# oled_control.net
KiCad netlist of a schematic drawn in Altium Designer
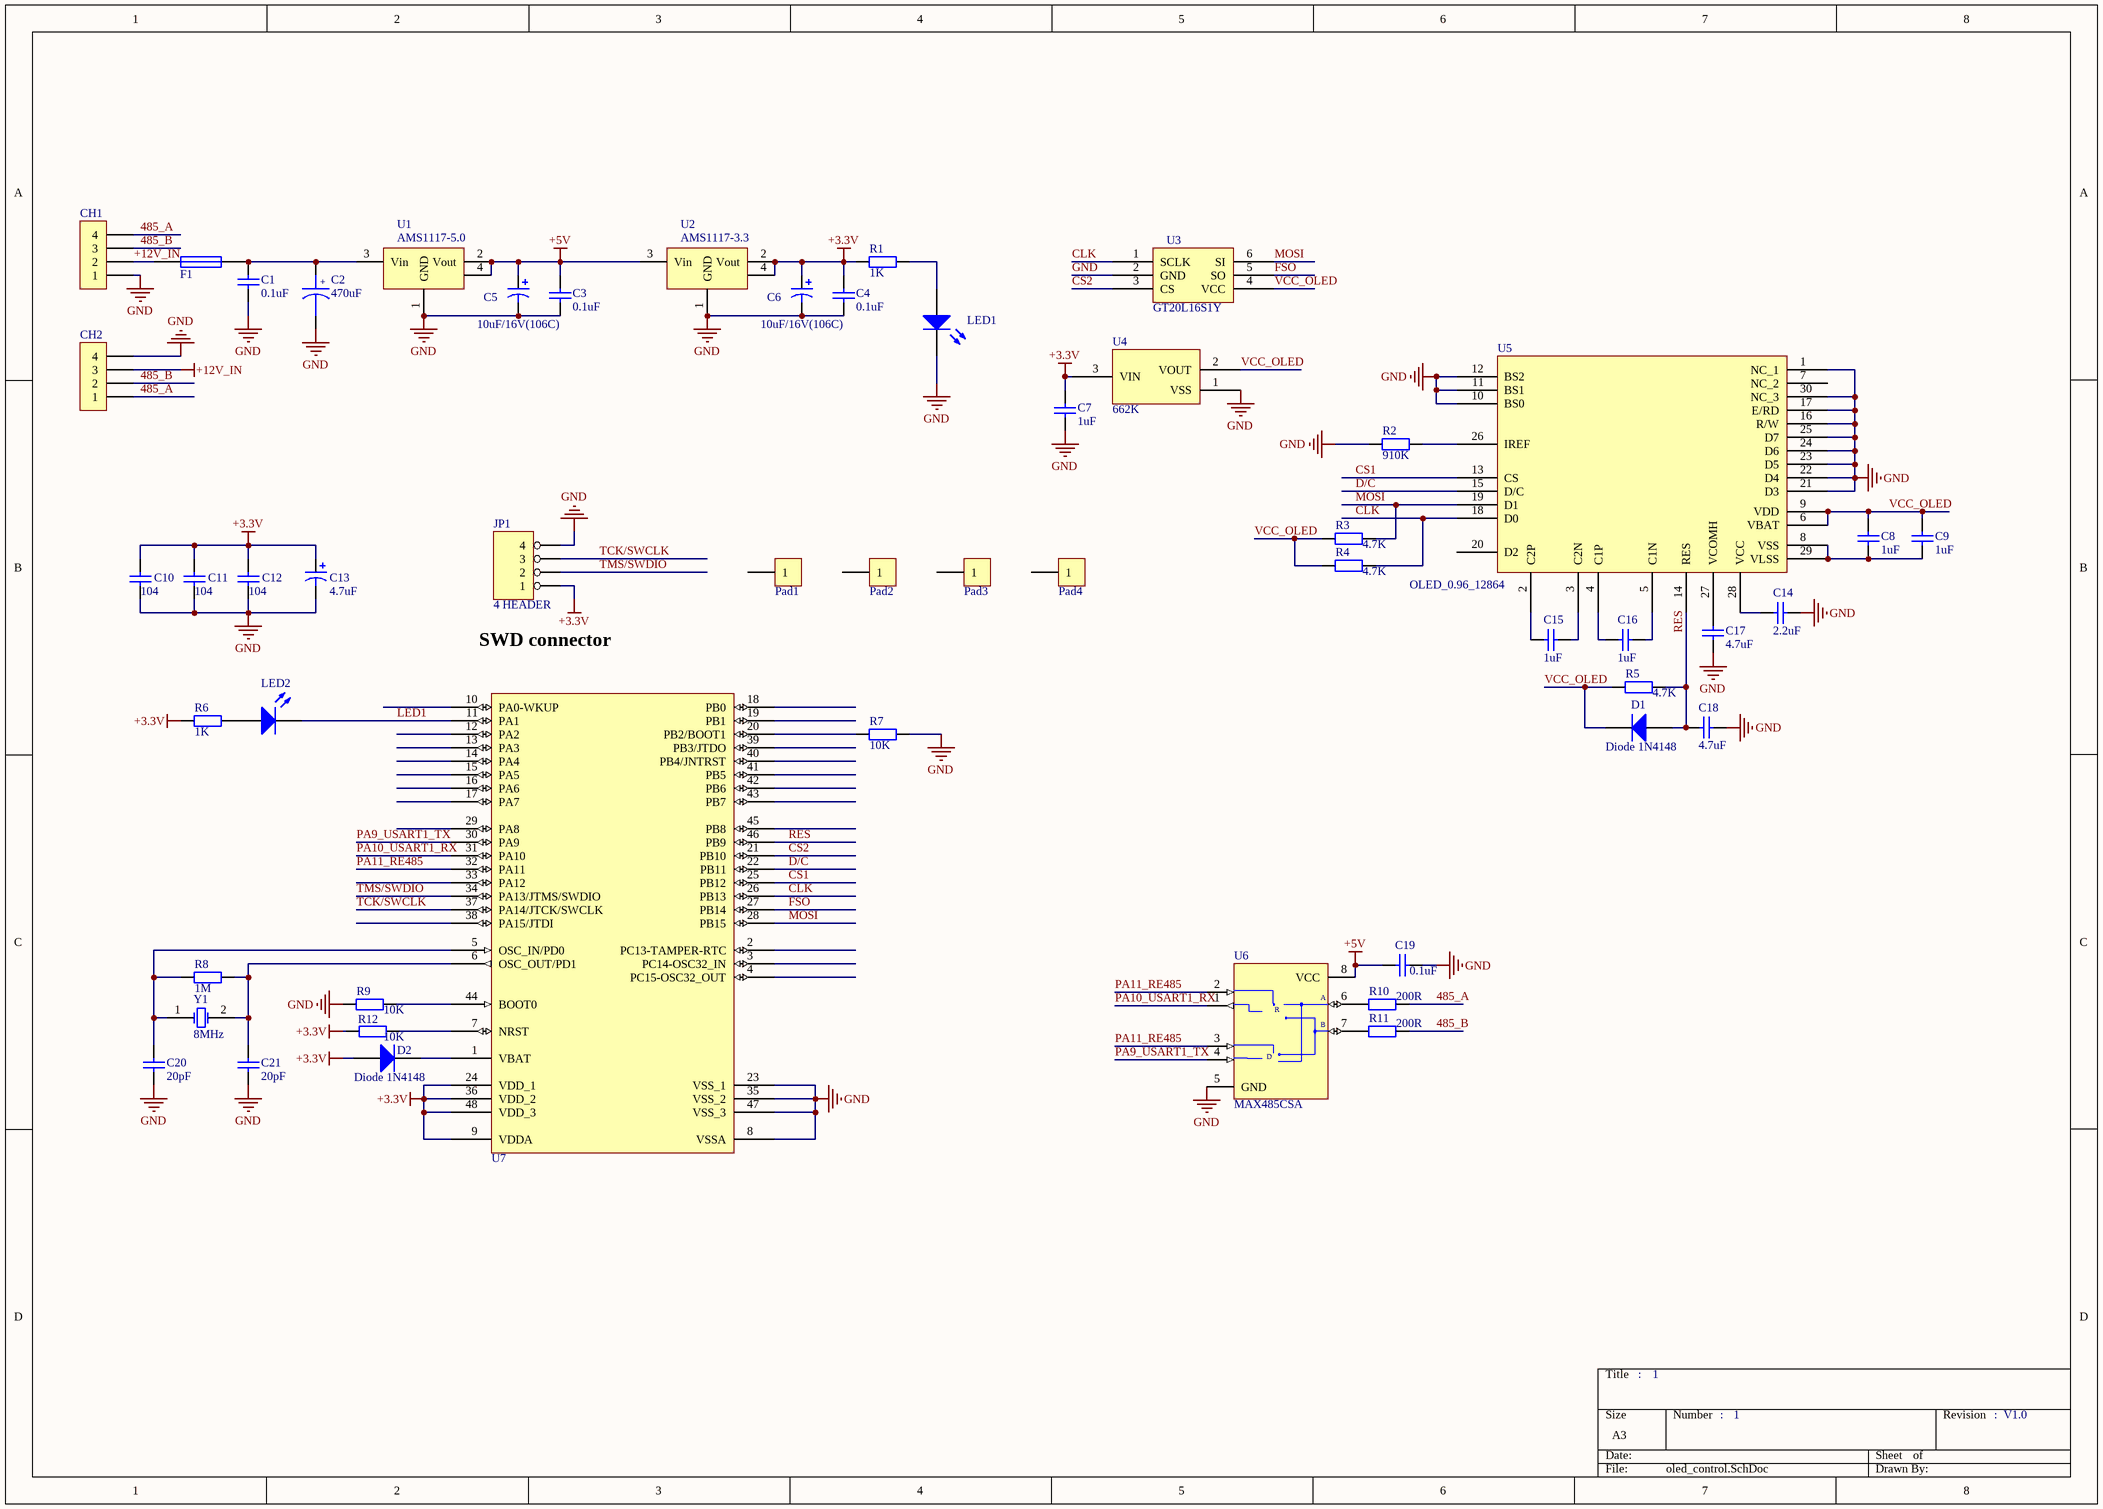
[diagram p0: oled_control.SchDoc]

(export (version "E")
  (design (tool "Eeschema 10.0.6"))
  (components
    (comp (ref "C1")
      (value "0.1uF")
      (footprint "0805")
      (description "Capacitor")
      (fields (field (name "Comment") "Cap") (field (name "PUBLISHER") "Altium Limited"))
      (libsource (lib "Miscellaneous Devices") (part "Cap"))
    )
    (comp (ref "C2")
      (value "C_2200uF")
      (footprint "C5*10")
      (fields (field (name "ALTIUM_UNNAMED_1") "470uF"))
      (libsource (lib "myIntegrated_Library1") (part "C_2200uF"))
    )
    (comp (ref "C3")
      (value "0.1uF")
      (footprint "0805")
      (description "Capacitor")
      (fields (field (name "Comment") "Cap") (field (name "PUBLISHER") "Altium Limited"))
      (libsource (lib "Miscellaneous Devices") (part "Cap"))
    )
    (comp (ref "C4")
      (value "0.1uF")
      (footprint "0805")
      (description "Capacitor")
      (fields (field (name "Comment") "Cap") (field (name "PUBLISHER") "Altium Limited"))
      (libsource (lib "Miscellaneous Devices") (part "Cap"))
    )
    (comp (ref "C5")
      (value "10uF/16V(106C)")
      (footprint "CAP A-3216")
      (description "Polarized Capacitor (Surface Mount)")
      (fields (field (name "Comment") "Cap Pol3") (field (name "PUBLISHER") "Altium Limited"))
      (libsource (lib "Miscellaneous Devices") (part "Cap Pol3"))
    )
    (comp (ref "C6")
      (value "10uF/16V(106C)")
      (footprint "CAP A-3216")
      (description "Polarized Capacitor (Surface Mount)")
      (fields (field (name "Comment") "Cap Pol3") (field (name "PUBLISHER") "Altium Limited"))
      (libsource (lib "Miscellaneous Devices") (part "Cap Pol3"))
    )
    (comp (ref "C7")
      (value "1uF")
      (footprint "0805")
      (description "Capacitor")
      (fields (field (name "Comment") "Cap") (field (name "PUBLISHER") "Altium Limited"))
      (libsource (lib "Miscellaneous Devices") (part "Cap"))
    )
    (comp (ref "C8")
      (value "1uF")
      (footprint "0805")
      (description "Capacitor")
      (fields (field (name "Comment") "Cap") (field (name "PUBLISHER") "Altium Limited"))
      (libsource (lib "Miscellaneous Devices") (part "Cap"))
    )
    (comp (ref "C9")
      (value "1uF")
      (footprint "0805")
      (description "Capacitor")
      (fields (field (name "Comment") "Cap") (field (name "PUBLISHER") "Altium Limited"))
      (libsource (lib "Miscellaneous Devices") (part "Cap"))
    )
    (comp (ref "C10")
      (value "104")
      (footprint "0805")
      (description "Capacitor")
      (fields (field (name "Comment") "Cap") (field (name "PUBLISHER") "Altium Limited"))
      (libsource (lib "Miscellaneous Devices") (part "Cap"))
    )
    (comp (ref "C11")
      (value "104")
      (footprint "0805")
      (description "Capacitor")
      (fields (field (name "Comment") "Cap") (field (name "PUBLISHER") "Altium Limited"))
      (libsource (lib "Miscellaneous Devices") (part "Cap"))
    )
    (comp (ref "C12")
      (value "104")
      (footprint "0805")
      (description "Capacitor")
      (fields (field (name "Comment") "Cap") (field (name "PUBLISHER") "Altium Limited"))
      (libsource (lib "Miscellaneous Devices") (part "Cap"))
    )
    (comp (ref "C13")
      (value "4.7uF")
      (footprint "3225[1210]")
      (description "Polarized Capacitor (Radial)")
      (fields (field (name "Comment") "Cap Pol1") (field (name "PUBLISHER") "Altium Limited"))
      (libsource (lib "Miscellaneous Devices") (part "Cap Pol1"))
    )
    (comp (ref "C14")
      (value "2.2uF")
      (footprint "0805")
      (description "Capacitor")
      (fields (field (name "Comment") "Cap") (field (name "PUBLISHER") "Altium Limited"))
      (libsource (lib "Miscellaneous Devices") (part "Cap"))
    )
    (comp (ref "C15")
      (value "1uF")
      (footprint "0805")
      (description "Capacitor")
      (fields (field (name "Comment") "Cap") (field (name "PUBLISHER") "Altium Limited"))
      (libsource (lib "Miscellaneous Devices") (part "Cap"))
    )
    (comp (ref "C16")
      (value "1uF")
      (footprint "0805")
      (description "Capacitor")
      (fields (field (name "Comment") "Cap") (field (name "PUBLISHER") "Altium Limited"))
      (libsource (lib "Miscellaneous Devices") (part "Cap"))
    )
    (comp (ref "C17")
      (value "4.7uF")
      (footprint "0805")
      (description "Capacitor")
      (fields (field (name "Comment") "Cap") (field (name "PUBLISHER") "Altium Limited"))
      (libsource (lib "Miscellaneous Devices") (part "Cap"))
    )
    (comp (ref "C18")
      (value "4.7uF")
      (footprint "0805")
      (description "Capacitor")
      (fields (field (name "Comment") "Cap") (field (name "PUBLISHER") "Altium Limited"))
      (libsource (lib "Miscellaneous Devices") (part "Cap"))
    )
    (comp (ref "C19")
      (value "0.1uF")
      (footprint "C0805tan")
      (description "Capacitor")
      (fields (field (name "Comment") "Cap") (field (name "PUBLISHER") "Altium Limited"))
      (libsource (lib "Miscellaneous Devices") (part "Cap"))
    )
    (comp (ref "C20")
      (value "20pF")
      (footprint "0805")
      (description "Capacitor")
      (fields (field (name "Comment") "Cap") (field (name "PUBLISHER") "Altium Limited"))
      (libsource (lib "开发板元件库") (part "Cap"))
    )
    (comp (ref "C21")
      (value "20pF")
      (footprint "0805")
      (description "Capacitor")
      (fields (field (name "Comment") "Cap") (field (name "PUBLISHER") "Altium Limited"))
      (libsource (lib "开发板元件库") (part "Cap"))
    )
    (comp (ref "CH1")
      (value "HEADER1X4")
      (footprint "CON4_1.5")
      (libsource (lib "myIntegrated_Library1") (part "HEADER1X4"))
    )
    (comp (ref "CH2")
      (value "HEADER1X4")
      (footprint "CON4_1.5")
      (libsource (lib "myIntegrated_Library1") (part "HEADER1X4"))
    )
    (comp (ref "D1")
      (value "Diode 1N4148")
      (footprint "LL34")
      (description "High Conductance Fast Diode")
      (fields (field (name "PUBLISHER") "Altium Limited"))
      (libsource (lib "Miscellaneous Devices") (part "Diode 1N4148"))
    )
    (comp (ref "D2")
      (value "Diode 1N4148")
      (footprint "LL34")
      (description "High Conductance Fast Diode")
      (fields (field (name "PUBLISHER") "Altium Limited"))
      (libsource (lib "Miscellaneous Devices") (part "Diode 1N4148"))
    )
    (comp (ref "F1")
      (value "FUSE")
      (footprint "3225[1210]")
      (libsource (lib "myIntegrated_Library1") (part "FUSE"))
    )
    (comp (ref "JP1")
      (value "4 HEADER")
      (footprint "CON4_1.5")
      (description "4 Pin Header")
      (libsource (lib "Miscellaneous Devices") (part "4 HEADER"))
    )
    (comp (ref "LED1")
      (value "~")
      (footprint "LED-0805")
      (description "Typical RED, GREEN, YELLOW, AMBER GaAs LED")
      (fields (field (name "PUBLISHER") "Altium Limited"))
      (libsource (lib "Miscellaneous Devices") (part "LED2"))
    )
    (comp (ref "LED2")
      (value "~")
      (footprint "LED-0805")
      (description "Typical RED, GREEN, YELLOW, AMBER GaAs LED")
      (fields (field (name "PUBLISHER") "Altium Limited"))
      (libsource (lib "Miscellaneous Devices") (part "LED2"))
    )
    (comp (ref "Pad1")
      (value "Pad")
      (footprint "pad35")
      (libsource (lib "myIntegrated_Library1") (part "Pad"))
    )
    (comp (ref "Pad2")
      (value "Pad")
      (footprint "pad35")
      (libsource (lib "myIntegrated_Library1") (part "Pad"))
    )
    (comp (ref "Pad3")
      (value "Pad")
      (footprint "pad35")
      (libsource (lib "myIntegrated_Library1") (part "Pad"))
    )
    (comp (ref "Pad4")
      (value "Pad")
      (footprint "pad35")
      (libsource (lib "myIntegrated_Library1") (part "Pad"))
    )
    (comp (ref "R1")
      (value "1K")
      (footprint "0805")
      (description "Resistor")
      (fields (field (name "Comment") "Res2") (field (name "PUBLISHER") "Altium Limited"))
      (libsource (lib "Miscellaneous Devices") (part "Res2"))
    )
    (comp (ref "R2")
      (value "910K")
      (footprint "0805")
      (description "Resistor")
      (fields (field (name "Comment") "Res2") (field (name "PUBLISHER") "Altium Limited"))
      (libsource (lib "Miscellaneous Devices") (part "Res2"))
    )
    (comp (ref "R3")
      (value "4.7K")
      (footprint "0805")
      (description "Resistor")
      (fields (field (name "Comment") "Res2") (field (name "PUBLISHER") "Altium Limited"))
      (libsource (lib "Miscellaneous Devices") (part "Res2"))
    )
    (comp (ref "R4")
      (value "4.7K")
      (footprint "0805")
      (description "Resistor")
      (fields (field (name "Comment") "Res2") (field (name "PUBLISHER") "Altium Limited"))
      (libsource (lib "Miscellaneous Devices") (part "Res2"))
    )
    (comp (ref "R5")
      (value "4.7K")
      (footprint "0805")
      (description "Resistor")
      (fields (field (name "Comment") "Res2") (field (name "PUBLISHER") "Altium Limited"))
      (libsource (lib "Miscellaneous Devices") (part "Res2"))
    )
    (comp (ref "R6")
      (value "1K")
      (footprint "0805")
      (description "Resistor")
      (fields (field (name "Comment") "Res2") (field (name "PUBLISHER") "Altium Limited"))
      (libsource (lib "Miscellaneous Devices") (part "Res2"))
    )
    (comp (ref "R7")
      (value "10K")
      (footprint "0805")
      (description "Resistor")
      (fields (field (name "Comment") "Res2") (field (name "PUBLISHER") "Altium Limited"))
      (libsource (lib "开发板元件库") (part "Res2"))
    )
    (comp (ref "R8")
      (value "1M")
      (footprint "0805")
      (description "Resistor")
      (fields (field (name "Comment") "Res2") (field (name "PUBLISHER") "Altium Limited"))
      (libsource (lib "开发板元件库") (part "Res2"))
    )
    (comp (ref "R9")
      (value "10K")
      (footprint "0805")
      (description "Resistor")
      (fields (field (name "Comment") "Res2") (field (name "PUBLISHER") "Altium Limited"))
      (libsource (lib "开发板元件库") (part "Res2"))
    )
    (comp (ref "R10")
      (value "200R")
      (footprint "C0805tan")
      (description "Resistor")
      (fields (field (name "Comment") "Res2") (field (name "PUBLISHER") "Altium Limited"))
      (libsource (lib "") (part "Res2_1"))
    )
    (comp (ref "R11")
      (value "200R")
      (footprint "C0805tan")
      (description "Resistor")
      (fields (field (name "Comment") "Res2") (field (name "PUBLISHER") "Altium Limited"))
      (libsource (lib "") (part "Res2_1"))
    )
    (comp (ref "R12")
      (value "10K")
      (footprint "0805")
      (description "Resistor")
      (fields (field (name "Comment") "Res2") (field (name "PUBLISHER") "Altium Limited"))
      (libsource (lib "开发板元件库") (part "Res2"))
    )
    (comp (ref "U1")
      (value "AMS1117-5.0")
      (footprint "SOT223")
      (libsource (lib "货架电子标签元件库") (part "AMS1117-5"))
    )
    (comp (ref "U2")
      (value "AMS1117-3.3")
      (footprint "SOT223")
      (libsource (lib "货架电子标签元件库") (part "AMS1117-5"))
    )
    (comp (ref "U3")
      (value "GT20L16S1Y")
      (footprint "SOT23-6")
      (libsource (lib "myIntegrated_Library1") (part "GT20L16S1Y"))
    )
    (comp (ref "U4")
      (value "662K")
      (footprint "SOT-23")
      (libsource (lib "myIntegrated_Library1") (part "662K"))
    )
    (comp (ref "U5")
      (value "OLED_0.96_12864")
      (footprint "OLED_0.96_12864")
      (libsource (lib "myIntegrated_Library1") (part "OLED_0.96_12864"))
    )
    (comp (ref "U6")
      (value "MAX485CSA")
      (footprint "NS08-L")
      (libsource (lib "myIntegrated_Library1") (part "MAX485CSA"))
    )
    (comp (ref "U7")
      (value "STM32F103C8T6")
      (footprint "LQFP48")
      (libsource (lib "myIntegrated_Library1") (part "STM32F103C8T6"))
    )
    (comp (ref "Y1")
      (value "8MHz")
      (footprint "XTAL_US")
      (description "Crystal Oscillator")
      (fields (field (name "PUBLISHER") "Altium Limited"))
      (libsource (lib "战舰STM32开发板底板封装库") (part "XTAL"))
    )
  )
  (nets
    (net (code "1") (name "+3.3V") (class "Default")
      (node (ref "C10") (pin "2") (pinfunction "2_2") (pintype "passive"))
      (node (ref "C11") (pin "2") (pinfunction "2_2") (pintype "passive"))
      (node (ref "C12") (pin "2") (pinfunction "2_2") (pintype "passive"))
      (node (ref "C13") (pin "1") (pinfunction "1_1") (pintype "passive"))
      (node (ref "C4") (pin "2") (pinfunction "2_2") (pintype "passive"))
      (node (ref "C6") (pin "1") (pinfunction "1_1") (pintype "passive"))
      (node (ref "C7") (pin "1") (pinfunction "1_1") (pintype "passive"))
      (node (ref "D2") (pin "1") (pinfunction "A_1") (pintype "passive"))
      (node (ref "JP1") (pin "1") (pinfunction "1_1") (pintype "passive"))
      (node (ref "R1") (pin "2") (pinfunction "2_2") (pintype "passive"))
      (node (ref "R12") (pin "1") (pinfunction "1_1") (pintype "passive"))
      (node (ref "R6") (pin "2") (pinfunction "2_2") (pintype "passive"))
      (node (ref "U2") (pin "2") (pinfunction "Vout_2") (pintype "passive"))
      (node (ref "U2") (pin "4") (pintype "passive"))
      (node (ref "U4") (pin "3") (pinfunction "VIN_3") (pintype "passive"))
      (node (ref "U7") (pin "24") (pinfunction "VDD_1_24") (pintype "power_in"))
      (node (ref "U7") (pin "36") (pinfunction "VDD_2_36") (pintype "power_in"))
      (node (ref "U7") (pin "48") (pinfunction "VDD_3_48") (pintype "power_in"))
      (node (ref "U7") (pin "9") (pinfunction "VDDA_9") (pintype "power_in"))
    )
    (net (code "2") (name "+5V") (class "Default")
      (node (ref "C19") (pin "1") (pinfunction "1_1") (pintype "passive"))
      (node (ref "C3") (pin "2") (pinfunction "2_2") (pintype "passive"))
      (node (ref "C5") (pin "1") (pinfunction "1_1") (pintype "passive"))
      (node (ref "U1") (pin "2") (pinfunction "Vout_2") (pintype "passive"))
      (node (ref "U1") (pin "4") (pintype "passive"))
      (node (ref "U2") (pin "3") (pinfunction "Vin_3") (pintype "passive"))
      (node (ref "U6") (pin "8") (pinfunction "VCC_8") (pintype "power_in"))
    )
    (net (code "3") (name "+12V_IN") (class "Default")
      (node (ref "CH1") (pin "2") (pinfunction "2_2") (pintype "passive"))
      (node (ref "CH2") (pin "3") (pinfunction "3_3") (pintype "passive"))
      (node (ref "F1") (pin "1") (pinfunction "1_1") (pintype "passive"))
    )
    (net (code "4") (name "/485_A") (class "Default")
      (node (ref "CH1") (pin "4") (pinfunction "4_4") (pintype "passive"))
      (node (ref "CH2") (pin "1") (pinfunction "1_1") (pintype "passive"))
      (node (ref "R10") (pin "2") (pinfunction "2_2") (pintype "passive"))
    )
    (net (code "5") (name "/485_B") (class "Default")
      (node (ref "CH1") (pin "3") (pinfunction "3_3") (pintype "passive"))
      (node (ref "CH2") (pin "2") (pinfunction "2_2") (pintype "passive"))
      (node (ref "R11") (pin "2") (pinfunction "2_2") (pintype "passive"))
    )
    (net (code "6") (name "/CLK") (class "Default")
      (node (ref "R4") (pin "1") (pinfunction "1_1") (pintype "passive"))
      (node (ref "U3") (pin "1") (pinfunction "SCLK_1") (pintype "passive"))
      (node (ref "U5") (pin "18") (pinfunction "D0_18") (pintype "passive"))
      (node (ref "U7") (pin "26") (pinfunction "PB13_26") (pintype "bidirectional"))
    )
    (net (code "7") (name "/CS1") (class "Default")
      (node (ref "U5") (pin "13") (pinfunction "CS_13") (pintype "passive"))
      (node (ref "U7") (pin "25") (pinfunction "PB12_25") (pintype "bidirectional"))
    )
    (net (code "8") (name "/CS2") (class "Default")
      (node (ref "U3") (pin "3") (pinfunction "CS_3") (pintype "passive"))
      (node (ref "U7") (pin "21") (pinfunction "PB10_21") (pintype "bidirectional"))
    )
    (net (code "9") (name "/D{slash}C") (class "Default")
      (node (ref "U5") (pin "15") (pinfunction "D/C_15") (pintype "passive"))
      (node (ref "U7") (pin "22") (pinfunction "PB11_22") (pintype "bidirectional"))
    )
    (net (code "10") (name "/FSO") (class "Default")
      (node (ref "U3") (pin "5") (pinfunction "SO_5") (pintype "passive"))
      (node (ref "U7") (pin "27") (pinfunction "PB14_27") (pintype "bidirectional"))
    )
    (net (code "11") (name "/LED1") (class "Default")
      (node (ref "LED2") (pin "2") (pinfunction "K_2") (pintype "passive"))
      (node (ref "U7") (pin "11") (pinfunction "PA1_11") (pintype "bidirectional"))
    )
    (net (code "12") (name "/MOSI") (class "Default")
      (node (ref "R3") (pin "1") (pinfunction "1_1") (pintype "passive"))
      (node (ref "U3") (pin "6") (pinfunction "SI_6") (pintype "passive"))
      (node (ref "U5") (pin "19") (pinfunction "D1_19") (pintype "passive"))
      (node (ref "U7") (pin "28") (pinfunction "PB15_28") (pintype "bidirectional"))
    )
    (net (code "13") (name "/PA9_USART1_TX") (class "Default")
      (node (ref "U6") (pin "4") (pinfunction "DI_4") (pintype "input"))
      (node (ref "U7") (pin "30") (pinfunction "PA9_30") (pintype "bidirectional"))
    )
    (net (code "14") (name "/PA10_USART1_RX") (class "Default")
      (node (ref "U6") (pin "1") (pinfunction "RO_1") (pintype "output"))
      (node (ref "U7") (pin "31") (pinfunction "PA10_31") (pintype "bidirectional"))
    )
    (net (code "15") (name "/PA11_RE485") (class "Default")
      (node (ref "U6") (pin "2") (pinfunction "~{RE}_2") (pintype "input"))
      (node (ref "U6") (pin "3") (pinfunction "DE_3") (pintype "input"))
      (node (ref "U7") (pin "32") (pinfunction "PA11_32") (pintype "bidirectional"))
    )
    (net (code "16") (name "/RES") (class "Default")
      (node (ref "C18") (pin "2") (pinfunction "2_2") (pintype "passive"))
      (node (ref "D1") (pin "1") (pinfunction "A_1") (pintype "passive"))
      (node (ref "R5") (pin "1") (pinfunction "1_1") (pintype "passive"))
      (node (ref "U5") (pin "14") (pinfunction "RES_14") (pintype "passive"))
      (node (ref "U7") (pin "46") (pinfunction "PB9_46") (pintype "bidirectional"))
    )
    (net (code "17") (name "/TCK{slash}SWCLK") (class "Default")
      (node (ref "JP1") (pin "3") (pinfunction "3_3") (pintype "passive"))
      (node (ref "U7") (pin "37") (pinfunction "PA14/JTCK/SWCLK_37") (pintype "bidirectional"))
    )
    (net (code "18") (name "/TMS{slash}SWDIO") (class "Default")
      (node (ref "JP1") (pin "2") (pinfunction "2_2") (pintype "passive"))
      (node (ref "U7") (pin "34") (pinfunction "PA13/JTMS/SWDIO_34") (pintype "bidirectional"))
    )
    (net (code "19") (name "/VCC_OLED") (class "Default")
      (node (ref "C8") (pin "1") (pinfunction "1_1") (pintype "passive"))
      (node (ref "C9") (pin "1") (pinfunction "1_1") (pintype "passive"))
      (node (ref "D1") (pin "2") (pinfunction "K_2") (pintype "passive"))
      (node (ref "R3") (pin "2") (pinfunction "2_2") (pintype "passive"))
      (node (ref "R4") (pin "2") (pinfunction "2_2") (pintype "passive"))
      (node (ref "R5") (pin "2") (pinfunction "2_2") (pintype "passive"))
      (node (ref "U3") (pin "4") (pinfunction "VCC_4") (pintype "passive"))
      (node (ref "U4") (pin "2") (pinfunction "VOUT_2") (pintype "passive"))
      (node (ref "U5") (pin "6") (pinfunction "VBAT_6") (pintype "passive"))
      (node (ref "U5") (pin "9") (pinfunction "VDD_9") (pintype "passive"))
    )
    (net (code "20") (name "GND") (class "Default")
      (node (ref "C1") (pin "1") (pinfunction "1_1") (pintype "passive"))
      (node (ref "C10") (pin "1") (pinfunction "1_1") (pintype "passive"))
      (node (ref "C11") (pin "1") (pinfunction "1_1") (pintype "passive"))
      (node (ref "C12") (pin "1") (pinfunction "1_1") (pintype "passive"))
      (node (ref "C13") (pin "2") (pinfunction "2_2") (pintype "passive"))
      (node (ref "C14") (pin "1") (pinfunction "1_1") (pintype "passive"))
      (node (ref "C17") (pin "2") (pinfunction "2_2") (pintype "passive"))
      (node (ref "C18") (pin "1") (pinfunction "1_1") (pintype "passive"))
      (node (ref "C19") (pin "2") (pinfunction "2_2") (pintype "passive"))
      (node (ref "C2") (pin "2") (pinfunction "2_2") (pintype "passive"))
      (node (ref "C20") (pin "1") (pinfunction "1_1") (pintype "passive"))
      (node (ref "C21") (pin "1") (pinfunction "1_1") (pintype "passive"))
      (node (ref "C3") (pin "1") (pinfunction "1_1") (pintype "passive"))
      (node (ref "C4") (pin "1") (pinfunction "1_1") (pintype "passive"))
      (node (ref "C5") (pin "2") (pinfunction "2_2") (pintype "passive"))
      (node (ref "C6") (pin "2") (pinfunction "2_2") (pintype "passive"))
      (node (ref "C7") (pin "2") (pinfunction "2_2") (pintype "passive"))
      (node (ref "CH1") (pin "1") (pinfunction "1_1") (pintype "passive"))
      (node (ref "CH2") (pin "4") (pinfunction "4_4") (pintype "passive"))
      (node (ref "JP1") (pin "4") (pinfunction "4_4") (pintype "passive"))
      (node (ref "LED1") (pin "2") (pinfunction "K_2") (pintype "passive"))
      (node (ref "R2") (pin "2") (pinfunction "2_2") (pintype "passive"))
      (node (ref "R7") (pin "2") (pinfunction "2_2") (pintype "passive"))
      (node (ref "R9") (pin "1") (pinfunction "1_1") (pintype "passive"))
      (node (ref "U1") (pin "1") (pinfunction "GND_1") (pintype "passive"))
      (node (ref "U2") (pin "1") (pinfunction "GND_1") (pintype "passive"))
      (node (ref "U3") (pin "2") (pinfunction "GND_2") (pintype "passive"))
      (node (ref "U4") (pin "1") (pinfunction "VSS_1") (pintype "passive"))
      (node (ref "U5") (pin "1") (pinfunction "NC_1_1") (pintype "passive"))
      (node (ref "U5") (pin "10") (pinfunction "BS0_10") (pintype "passive"))
      (node (ref "U5") (pin "11") (pinfunction "BS1_11") (pintype "passive"))
      (node (ref "U5") (pin "12") (pinfunction "BS2_12") (pintype "passive"))
      (node (ref "U5") (pin "16") (pinfunction "R/W_16") (pintype "passive"))
      (node (ref "U5") (pin "17") (pinfunction "E/RD_17") (pintype "passive"))
      (node (ref "U5") (pin "21") (pinfunction "D3_21") (pintype "passive"))
      (node (ref "U5") (pin "22") (pinfunction "D4_22") (pintype "passive"))
      (node (ref "U5") (pin "23") (pinfunction "D5_23") (pintype "passive"))
      (node (ref "U5") (pin "24") (pinfunction "D6_24") (pintype "passive"))
      (node (ref "U5") (pin "25") (pinfunction "D7_25") (pintype "passive"))
      (node (ref "U5") (pin "30") (pinfunction "NC_3_30") (pintype "passive"))
      (node (ref "U6") (pin "5") (pinfunction "GND_5") (pintype "power_in"))
      (node (ref "U7") (pin "23") (pinfunction "VSS_1_23") (pintype "power_in"))
      (node (ref "U7") (pin "35") (pinfunction "VSS_2_35") (pintype "power_in"))
      (node (ref "U7") (pin "47") (pinfunction "VSS_3_47") (pintype "power_in"))
      (node (ref "U7") (pin "8") (pinfunction "VSSA_8") (pintype "power_in"))
    )
    (net (code "21") (name "Net-(D2-K)") (class "Default")
      (node (ref "D2") (pin "2") (pinfunction "K_2") (pintype "passive"))
      (node (ref "U7") (pin "1") (pinfunction "VBAT_1") (pintype "power_in"))
    )
    (net (code "22") (name "Net-(LED1-A)") (class "Default")
      (node (ref "LED1") (pin "1") (pinfunction "A_1") (pintype "passive"))
      (node (ref "R1") (pin "1") (pinfunction "1_1") (pintype "passive"))
    )
    (net (code "23") (name "Net-(LED2-A)") (class "Default")
      (node (ref "LED2") (pin "1") (pinfunction "A_1") (pintype "passive"))
      (node (ref "R6") (pin "1") (pinfunction "1_1") (pintype "passive"))
    )
    (net (code "24") (name "Net-(U1-Vin)") (class "Default")
      (node (ref "C1") (pin "2") (pinfunction "2_2") (pintype "passive"))
      (node (ref "C2") (pin "1") (pinfunction "1_1") (pintype "passive"))
      (node (ref "F1") (pin "2") (pinfunction "2_2") (pintype "passive"))
      (node (ref "U1") (pin "3") (pinfunction "Vin_3") (pintype "passive"))
    )
    (net (code "25") (name "Net-(U5-C1N)") (class "Default")
      (node (ref "C16") (pin "1") (pinfunction "1_1") (pintype "passive"))
      (node (ref "U5") (pin "5") (pinfunction "C1N_5") (pintype "passive"))
    )
    (net (code "26") (name "Net-(U5-C1P)") (class "Default")
      (node (ref "C16") (pin "2") (pinfunction "2_2") (pintype "passive"))
      (node (ref "U5") (pin "4") (pinfunction "C1P_4") (pintype "passive"))
    )
    (net (code "27") (name "Net-(U5-C2N)") (class "Default")
      (node (ref "C15") (pin "1") (pinfunction "1_1") (pintype "passive"))
      (node (ref "U5") (pin "3") (pinfunction "C2N_3") (pintype "passive"))
    )
    (net (code "28") (name "Net-(U5-C2P)") (class "Default")
      (node (ref "C15") (pin "2") (pinfunction "2_2") (pintype "passive"))
      (node (ref "U5") (pin "2") (pinfunction "C2P_2") (pintype "passive"))
    )
    (net (code "29") (name "Net-(U5-IREF)") (class "Default")
      (node (ref "R2") (pin "1") (pinfunction "1_1") (pintype "passive"))
      (node (ref "U5") (pin "26") (pinfunction "IREF_26") (pintype "passive"))
    )
    (net (code "30") (name "Net-(U5-VCC)") (class "Default")
      (node (ref "C14") (pin "2") (pinfunction "2_2") (pintype "passive"))
      (node (ref "U5") (pin "28") (pinfunction "VCC_28") (pintype "passive"))
    )
    (net (code "31") (name "Net-(U5-VCOMH)") (class "Default")
      (node (ref "C17") (pin "1") (pinfunction "1_1") (pintype "passive"))
      (node (ref "U5") (pin "27") (pinfunction "VCOMH_27") (pintype "passive"))
    )
    (net (code "32") (name "Net-(U5-VLSS)") (class "Default")
      (node (ref "C8") (pin "2") (pinfunction "2_2") (pintype "passive"))
      (node (ref "C9") (pin "2") (pinfunction "2_2") (pintype "passive"))
      (node (ref "U5") (pin "29") (pinfunction "VLSS_29") (pintype "passive"))
      (node (ref "U5") (pin "8") (pinfunction "VSS_8") (pintype "passive"))
    )
    (net (code "33") (name "Net-(U6-A)") (class "Default")
      (node (ref "R10") (pin "1") (pinfunction "1_1") (pintype "passive"))
      (node (ref "U6") (pin "6") (pinfunction "A_6") (pintype "bidirectional"))
    )
    (net (code "34") (name "Net-(U6-B)") (class "Default")
      (node (ref "R11") (pin "1") (pinfunction "1_1") (pintype "passive"))
      (node (ref "U6") (pin "7") (pinfunction "B_7") (pintype "bidirectional"))
    )
    (net (code "35") (name "Net-(U7-BOOT0)") (class "Default")
      (node (ref "R9") (pin "2") (pinfunction "2_2") (pintype "passive"))
      (node (ref "U7") (pin "44") (pinfunction "BOOT0_44") (pintype "input"))
    )
    (net (code "36") (name "Net-(U7-NRST)") (class "Default")
      (node (ref "R12") (pin "2") (pinfunction "2_2") (pintype "passive"))
      (node (ref "U7") (pin "7") (pinfunction "NRST_7") (pintype "bidirectional"))
    )
    (net (code "37") (name "Net-(U7-OSC_IN{slash}PD0)") (class "Default")
      (node (ref "C20") (pin "2") (pinfunction "2_2") (pintype "passive"))
      (node (ref "R8") (pin "1") (pinfunction "1_1") (pintype "passive"))
      (node (ref "U7") (pin "5") (pinfunction "OSC_IN/PD0_5") (pintype "input"))
      (node (ref "Y1") (pin "1") (pinfunction "OSC1_1") (pintype "passive"))
    )
    (net (code "38") (name "Net-(U7-OSC_OUT{slash}PD1)") (class "Default")
      (node (ref "C21") (pin "2") (pinfunction "2_2") (pintype "passive"))
      (node (ref "R8") (pin "2") (pinfunction "2_2") (pintype "passive"))
      (node (ref "U7") (pin "6") (pinfunction "OSC_OUT/PD1_6") (pintype "output"))
      (node (ref "Y1") (pin "2") (pinfunction "OSC2_2") (pintype "passive"))
    )
    (net (code "39") (name "Net-(U7-PB2{slash}BOOT1)") (class "Default")
      (node (ref "R7") (pin "1") (pinfunction "1_1") (pintype "passive"))
      (node (ref "U7") (pin "20") (pinfunction "PB2/BOOT1_20") (pintype "bidirectional"))
    )
    (net (code "40") (name "unconnected-(Pad1-Pad1)") (class "Default")
      (node (ref "Pad1") (pin "1") (pinfunction "1_1") (pintype "passive"))
    )
    (net (code "41") (name "unconnected-(Pad2-Pad1)") (class "Default")
      (node (ref "Pad2") (pin "1") (pinfunction "1_1") (pintype "passive"))
    )
    (net (code "42") (name "unconnected-(Pad3-Pad1)") (class "Default")
      (node (ref "Pad3") (pin "1") (pinfunction "1_1") (pintype "passive"))
    )
    (net (code "43") (name "unconnected-(Pad4-Pad1)") (class "Default")
      (node (ref "Pad4") (pin "1") (pinfunction "1_1") (pintype "passive"))
    )
    (net (code "44") (name "unconnected-(U5-D2-Pad20)") (class "Default")
      (node (ref "U5") (pin "20") (pinfunction "D2_20") (pintype "passive"))
    )
    (net (code "45") (name "unconnected-(U5-NC_2-Pad7)") (class "Default")
      (node (ref "U5") (pin "7") (pinfunction "NC_2_7") (pintype "passive"))
    )
    (net (code "46") (name "unconnected-(U7-PA0-WKUP-Pad10)") (class "Default")
      (node (ref "U7") (pin "10") (pinfunction "PA0-WKUP_10") (pintype "bidirectional"))
    )
    (net (code "47") (name "unconnected-(U7-PA2-Pad12)") (class "Default")
      (node (ref "U7") (pin "12") (pinfunction "PA2_12") (pintype "bidirectional"))
    )
    (net (code "48") (name "unconnected-(U7-PA3-Pad13)") (class "Default")
      (node (ref "U7") (pin "13") (pinfunction "PA3_13") (pintype "bidirectional"))
    )
    (net (code "49") (name "unconnected-(U7-PA4-Pad14)") (class "Default")
      (node (ref "U7") (pin "14") (pinfunction "PA4_14") (pintype "bidirectional"))
    )
    (net (code "50") (name "unconnected-(U7-PA5-Pad15)") (class "Default")
      (node (ref "U7") (pin "15") (pinfunction "PA5_15") (pintype "bidirectional"))
    )
    (net (code "51") (name "unconnected-(U7-PA6-Pad16)") (class "Default")
      (node (ref "U7") (pin "16") (pinfunction "PA6_16") (pintype "bidirectional"))
    )
    (net (code "52") (name "unconnected-(U7-PA7-Pad17)") (class "Default")
      (node (ref "U7") (pin "17") (pinfunction "PA7_17") (pintype "bidirectional"))
    )
    (net (code "53") (name "unconnected-(U7-PA8-Pad29)") (class "Default")
      (node (ref "U7") (pin "29") (pinfunction "PA8_29") (pintype "bidirectional"))
    )
    (net (code "54") (name "unconnected-(U7-PA12-Pad33)") (class "Default")
      (node (ref "U7") (pin "33") (pinfunction "PA12_33") (pintype "bidirectional"))
    )
    (net (code "55") (name "unconnected-(U7-PA15{slash}JTDI-Pad38)") (class "Default")
      (node (ref "U7") (pin "38") (pinfunction "PA15/JTDI_38") (pintype "bidirectional"))
    )
    (net (code "56") (name "unconnected-(U7-PB0-Pad18)") (class "Default")
      (node (ref "U7") (pin "18") (pinfunction "PB0_18") (pintype "bidirectional"))
    )
    (net (code "57") (name "unconnected-(U7-PB1-Pad19)") (class "Default")
      (node (ref "U7") (pin "19") (pinfunction "PB1_19") (pintype "bidirectional"))
    )
    (net (code "58") (name "unconnected-(U7-PB3{slash}JTDO-Pad39)") (class "Default")
      (node (ref "U7") (pin "39") (pinfunction "PB3/JTDO_39") (pintype "bidirectional"))
    )
    (net (code "59") (name "unconnected-(U7-PB4{slash}JNTRST-Pad40)") (class "Default")
      (node (ref "U7") (pin "40") (pinfunction "PB4/JNTRST_40") (pintype "bidirectional"))
    )
    (net (code "60") (name "unconnected-(U7-PB5-Pad41)") (class "Default")
      (node (ref "U7") (pin "41") (pinfunction "PB5_41") (pintype "bidirectional"))
    )
    (net (code "61") (name "unconnected-(U7-PB6-Pad42)") (class "Default")
      (node (ref "U7") (pin "42") (pinfunction "PB6_42") (pintype "bidirectional"))
    )
    (net (code "62") (name "unconnected-(U7-PB7-Pad43)") (class "Default")
      (node (ref "U7") (pin "43") (pinfunction "PB7_43") (pintype "bidirectional"))
    )
    (net (code "63") (name "unconnected-(U7-PB8-Pad45)") (class "Default")
      (node (ref "U7") (pin "45") (pinfunction "PB8_45") (pintype "bidirectional"))
    )
    (net (code "64") (name "unconnected-(U7-PC13-TAMPER-RTC-Pad2)") (class "Default")
      (node (ref "U7") (pin "2") (pinfunction "PC13-TAMPER-RTC_2") (pintype "bidirectional"))
    )
    (net (code "65") (name "unconnected-(U7-PC14-OSC32_IN-Pad3)") (class "Default")
      (node (ref "U7") (pin "3") (pinfunction "PC14-OSC32_IN_3") (pintype "bidirectional"))
    )
    (net (code "66") (name "unconnected-(U7-PC15-OSC32_OUT-Pad4)") (class "Default")
      (node (ref "U7") (pin "4") (pinfunction "PC15-OSC32_OUT_4") (pintype "bidirectional"))
    )
  )
)
